# STM32F4xxZ.net
KiCad netlist of a schematic drawn in Altium Designer
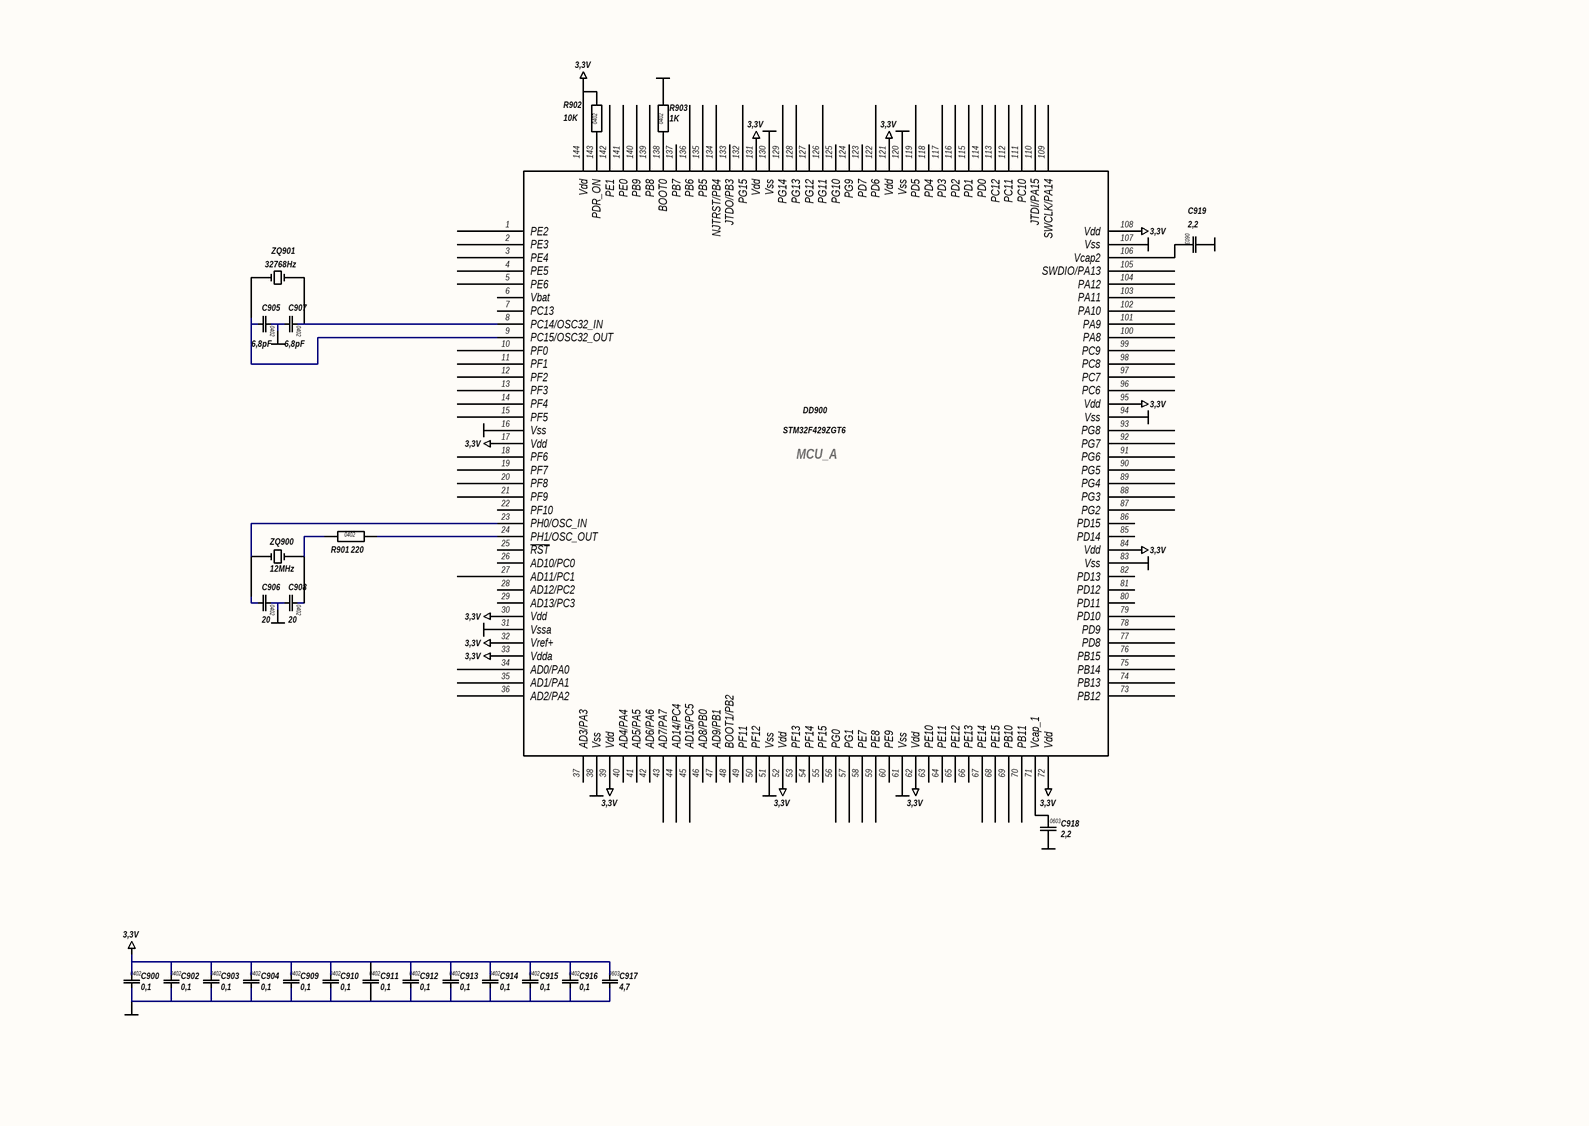
[diagram p0: STM32F4xxZ.SchDoc]

(export (version "E")
  (design (tool "Eeschema 10.0.6"))
  (components
    (comp (ref "C900")
      (value "0,1")
      (footprint "CAP0402")
      (description "Конденсатор чип")
      (libsource (lib "EwgPassive") (part "CAP_0402"))
    )
    (comp (ref "C902")
      (value "0,1")
      (footprint "CAP0402")
      (description "Конденсатор чип")
      (libsource (lib "EwgPassive") (part "CAP_0402"))
    )
    (comp (ref "C903")
      (value "0,1")
      (footprint "CAP0402")
      (description "Конденсатор чип")
      (libsource (lib "EwgPassive") (part "CAP_0402"))
    )
    (comp (ref "C904")
      (value "0,1")
      (footprint "CAP0402")
      (description "Конденсатор чип")
      (libsource (lib "EwgPassive") (part "CAP_0402"))
    )
    (comp (ref "C905")
      (value "6,8pF")
      (footprint "CAP0402")
      (description "Конденсатор чип")
      (libsource (lib "EwgPassive") (part "CAP_0402"))
    )
    (comp (ref "C906")
      (value "20")
      (footprint "CAP0402")
      (description "Конденсатор чип")
      (libsource (lib "EwgPassive") (part "CAP_0402"))
    )
    (comp (ref "C907")
      (value "6,8pF")
      (footprint "CAP0402")
      (description "Конденсатор чип")
      (libsource (lib "EwgPassive") (part "CAP_0402"))
    )
    (comp (ref "C908")
      (value "20")
      (footprint "CAP0402")
      (description "Конденсатор чип")
      (libsource (lib "EwgPassive") (part "CAP_0402"))
    )
    (comp (ref "C909")
      (value "0,1")
      (footprint "CAP0402")
      (description "Конденсатор чип")
      (libsource (lib "EwgPassive") (part "CAP_0402"))
    )
    (comp (ref "C910")
      (value "0,1")
      (footprint "CAP0402")
      (description "Конденсатор чип")
      (libsource (lib "EwgPassive") (part "CAP_0402"))
    )
    (comp (ref "C911")
      (value "0,1")
      (footprint "CAP0402")
      (description "Конденсатор чип")
      (libsource (lib "EwgPassive") (part "CAP_0402"))
    )
    (comp (ref "C912")
      (value "0,1")
      (footprint "CAP0402")
      (description "Конденсатор чип")
      (libsource (lib "EwgPassive") (part "CAP_0402"))
    )
    (comp (ref "C913")
      (value "0,1")
      (footprint "CAP0402")
      (description "Конденсатор чип")
      (libsource (lib "EwgPassive") (part "CAP_0402"))
    )
    (comp (ref "C914")
      (value "0,1")
      (footprint "CAP0402")
      (description "Конденсатор чип")
      (libsource (lib "EwgPassive") (part "CAP_0402"))
    )
    (comp (ref "C915")
      (value "0,1")
      (footprint "CAP0402")
      (description "Конденсатор чип")
      (libsource (lib "EwgPassive") (part "CAP_0402"))
    )
    (comp (ref "C916")
      (value "0,1")
      (footprint "CAP0402")
      (description "Конденсатор чип")
      (libsource (lib "EwgPassive") (part "CAP_0402"))
    )
    (comp (ref "C917")
      (value "4,7")
      (footprint "CAP0603")
      (description "Конденсатор чип")
      (libsource (lib "EwgPassive") (part "CAP_0603"))
    )
    (comp (ref "C918")
      (value "2,2")
      (footprint "CAP0603")
      (description "Конденсатор чип")
      (libsource (lib "EwgPassive") (part "CAP_0603"))
    )
    (comp (ref "C919")
      (value "2,2")
      (footprint "CAP0603")
      (description "Конденсатор чип")
      (libsource (lib "EwgPassive") (part "CAP_0603"))
    )
    (comp (ref "DD900")
      (value "STM32F429ZGT6")
      (footprint "LQFP144")
      (description "Микроконтроллер")
      (libsource (lib "EwgMicrochips") (part "STM32F4xxZ"))
    )
    (comp (ref "R901")
      (value "220")
      (footprint "RES0402")
      (description "Резистор чип")
      (libsource (lib "EwgPassive") (part "RES_0402"))
    )
    (comp (ref "R902")
      (value "10K")
      (footprint "RES0402")
      (description "Резистор чип")
      (libsource (lib "EwgPassive") (part "RES_0402"))
    )
    (comp (ref "R903")
      (value "1K")
      (footprint "RES0402")
      (description "Резистор чип")
      (libsource (lib "") (part "RES_0402_1"))
    )
    (comp (ref "ZQ900")
      (value "12MHz")
      (footprint "KX-7")
      (description "Кварц")
      (libsource (lib "EwgPassive") (part "KX-7"))
    )
    (comp (ref "ZQ901")
      (value "32768Hz")
      (footprint "OSC РК206 AA SMD")
      (description "Кварц")
      (libsource (lib "EwgPassive") (part "OSC РК206 AA 32.768KHZ"))
    )
  )
  (nets
    (net (code "1") (name "3,3V") (class "Default")
      (node (ref "C900") (pin "1") (pintype "passive"))
      (node (ref "C902") (pin "1") (pintype "passive"))
      (node (ref "C903") (pin "1") (pintype "passive"))
      (node (ref "C904") (pin "1") (pintype "passive"))
      (node (ref "C909") (pin "1") (pintype "passive"))
      (node (ref "C910") (pin "1") (pintype "passive"))
      (node (ref "C911") (pin "1") (pintype "passive"))
      (node (ref "C912") (pin "1") (pintype "passive"))
      (node (ref "C913") (pin "1") (pintype "passive"))
      (node (ref "C914") (pin "1") (pintype "passive"))
      (node (ref "C915") (pin "1") (pintype "passive"))
      (node (ref "C916") (pin "1") (pintype "passive"))
      (node (ref "C917") (pin "1") (pintype "passive"))
      (node (ref "DD900") (pin "108") (pinfunction "Vdd_108") (pintype "passive"))
      (node (ref "DD900") (pin "121") (pinfunction "Vdd_121") (pintype "passive"))
      (node (ref "DD900") (pin "131") (pinfunction "Vdd_131") (pintype "passive"))
      (node (ref "DD900") (pin "144") (pinfunction "Vdd_144") (pintype "passive"))
      (node (ref "DD900") (pin "17") (pinfunction "Vdd_17") (pintype "passive"))
      (node (ref "DD900") (pin "30") (pinfunction "Vdd_30") (pintype "passive"))
      (node (ref "DD900") (pin "32") (pinfunction "Vref+_32") (pintype "passive"))
      (node (ref "DD900") (pin "33") (pinfunction "Vdda_33") (pintype "passive"))
      (node (ref "DD900") (pin "39") (pinfunction "Vdd_39") (pintype "passive"))
      (node (ref "DD900") (pin "52") (pinfunction "Vdd_52") (pintype "passive"))
      (node (ref "DD900") (pin "62") (pinfunction "Vdd_62") (pintype "passive"))
      (node (ref "DD900") (pin "72") (pinfunction "Vdd_72") (pintype "passive"))
      (node (ref "DD900") (pin "84") (pinfunction "Vdd_84") (pintype "passive"))
      (node (ref "DD900") (pin "95") (pinfunction "Vdd_95") (pintype "passive"))
      (node (ref "R902") (pin "2") (pintype "passive"))
    )
    (net (code "2") (name "GND") (class "Default")
      (node (ref "C900") (pin "2") (pintype "passive"))
      (node (ref "C902") (pin "2") (pintype "passive"))
      (node (ref "C903") (pin "2") (pintype "passive"))
      (node (ref "C904") (pin "2") (pintype "passive"))
      (node (ref "C905") (pin "1") (pintype "passive"))
      (node (ref "C906") (pin "1") (pintype "passive"))
      (node (ref "C907") (pin "2") (pintype "passive"))
      (node (ref "C908") (pin "2") (pintype "passive"))
      (node (ref "C909") (pin "2") (pintype "passive"))
      (node (ref "C910") (pin "2") (pintype "passive"))
      (node (ref "C911") (pin "2") (pintype "passive"))
      (node (ref "C912") (pin "2") (pintype "passive"))
      (node (ref "C913") (pin "2") (pintype "passive"))
      (node (ref "C914") (pin "2") (pintype "passive"))
      (node (ref "C915") (pin "2") (pintype "passive"))
      (node (ref "C916") (pin "2") (pintype "passive"))
      (node (ref "C917") (pin "2") (pintype "passive"))
      (node (ref "C918") (pin "2") (pintype "passive"))
      (node (ref "C919") (pin "2") (pintype "passive"))
      (node (ref "DD900") (pin "107") (pinfunction "Vss_107") (pintype "passive"))
      (node (ref "DD900") (pin "120") (pinfunction "Vss_120") (pintype "passive"))
      (node (ref "DD900") (pin "130") (pinfunction "Vss_130") (pintype "passive"))
      (node (ref "DD900") (pin "16") (pinfunction "Vss_16") (pintype "passive"))
      (node (ref "DD900") (pin "31") (pinfunction "Vssa_31") (pintype "passive"))
      (node (ref "DD900") (pin "38") (pinfunction "Vss_38") (pintype "passive"))
      (node (ref "DD900") (pin "51") (pinfunction "Vss_51") (pintype "passive"))
      (node (ref "DD900") (pin "61") (pinfunction "Vss_61") (pintype "passive"))
      (node (ref "DD900") (pin "83") (pinfunction "Vss_83") (pintype "passive"))
      (node (ref "DD900") (pin "94") (pinfunction "Vss_94") (pintype "passive"))
      (node (ref "R903") (pin "2") (pintype "passive"))
    )
    (net (code "3") (name "Net-(C908-Pad1)") (class "Default")
      (node (ref "C908") (pin "1") (pintype "passive"))
      (node (ref "R901") (pin "1") (pintype "passive"))
      (node (ref "ZQ900") (pin "1") (pintype "passive"))
    )
    (net (code "4") (name "Net-(DD900-BOOT0)") (class "Default")
      (node (ref "DD900") (pin "138") (pinfunction "BOOT0_138") (pintype "passive"))
      (node (ref "R903") (pin "1") (pintype "passive"))
    )
    (net (code "5") (name "Net-(DD900-PC14{slash}OSC32_IN)") (class "Default")
      (node (ref "C907") (pin "1") (pintype "passive"))
      (node (ref "DD900") (pin "8") (pinfunction "PC14/OSC32_IN_8") (pintype "passive"))
      (node (ref "ZQ901") (pin "1") (pintype "passive"))
    )
    (net (code "6") (name "Net-(DD900-PC15{slash}OSC32_OUT)") (class "Default")
      (node (ref "C905") (pin "2") (pintype "passive"))
      (node (ref "DD900") (pin "9") (pinfunction "PC15/OSC32_OUT_9") (pintype "passive"))
      (node (ref "ZQ901") (pin "2") (pintype "passive"))
    )
    (net (code "7") (name "Net-(DD900-PDR_ON)") (class "Default")
      (node (ref "DD900") (pin "143") (pinfunction "PDR_ON_143") (pintype "passive"))
      (node (ref "R902") (pin "1") (pintype "passive"))
    )
    (net (code "8") (name "Net-(DD900-PH0{slash}OSC_IN)") (class "Default")
      (node (ref "C906") (pin "2") (pintype "passive"))
      (node (ref "DD900") (pin "23") (pinfunction "PH0/OSC_IN_23") (pintype "passive"))
      (node (ref "ZQ900") (pin "3") (pintype "passive"))
    )
    (net (code "9") (name "Net-(DD900-PH1{slash}OSC_OUT)") (class "Default")
      (node (ref "DD900") (pin "24") (pinfunction "PH1/OSC_OUT_24") (pintype "passive"))
      (node (ref "R901") (pin "2") (pintype "passive"))
    )
    (net (code "10") (name "Net-(DD900-Vcap2)") (class "Default")
      (node (ref "C919") (pin "1") (pintype "passive"))
      (node (ref "DD900") (pin "106") (pinfunction "Vcap2_106") (pintype "passive"))
    )
    (net (code "11") (name "Net-(DD900-Vcap_1)") (class "Default")
      (node (ref "C918") (pin "1") (pintype "passive"))
      (node (ref "DD900") (pin "71") (pinfunction "Vcap_1_71") (pintype "passive"))
    )
    (net (code "12") (name "unconnected-(DD900-AD0{slash}PA0-Pad34)") (class "Default")
      (node (ref "DD900") (pin "34") (pinfunction "AD0/PA0_34") (pintype "passive"))
    )
    (net (code "13") (name "unconnected-(DD900-AD1{slash}PA1-Pad35)") (class "Default")
      (node (ref "DD900") (pin "35") (pinfunction "AD1/PA1_35") (pintype "passive"))
    )
    (net (code "14") (name "unconnected-(DD900-AD2{slash}PA2-Pad36)") (class "Default")
      (node (ref "DD900") (pin "36") (pinfunction "AD2/PA2_36") (pintype "passive"))
    )
    (net (code "15") (name "unconnected-(DD900-AD3{slash}PA3-Pad37)") (class "Default")
      (node (ref "DD900") (pin "37") (pinfunction "AD3/PA3_37") (pintype "passive"))
    )
    (net (code "16") (name "unconnected-(DD900-AD4{slash}PA4-Pad40)") (class "Default")
      (node (ref "DD900") (pin "40") (pinfunction "AD4/PA4_40") (pintype "passive"))
    )
    (net (code "17") (name "unconnected-(DD900-AD5{slash}PA5-Pad41)") (class "Default")
      (node (ref "DD900") (pin "41") (pinfunction "AD5/PA5_41") (pintype "passive"))
    )
    (net (code "18") (name "unconnected-(DD900-AD6{slash}PA6-Pad42)") (class "Default")
      (node (ref "DD900") (pin "42") (pinfunction "AD6/PA6_42") (pintype "passive"))
    )
    (net (code "19") (name "unconnected-(DD900-AD7{slash}PA7-Pad43)") (class "Default")
      (node (ref "DD900") (pin "43") (pinfunction "AD7/PA7_43") (pintype "passive"))
    )
    (net (code "20") (name "unconnected-(DD900-AD8{slash}PB0-Pad46)") (class "Default")
      (node (ref "DD900") (pin "46") (pinfunction "AD8/PB0_46") (pintype "passive"))
    )
    (net (code "21") (name "unconnected-(DD900-AD9{slash}PB1-Pad47)") (class "Default")
      (node (ref "DD900") (pin "47") (pinfunction "AD9/PB1_47") (pintype "passive"))
    )
    (net (code "22") (name "unconnected-(DD900-AD10{slash}PC0-Pad26)") (class "Default")
      (node (ref "DD900") (pin "26") (pinfunction "AD10/PC0_26") (pintype "passive"))
    )
    (net (code "23") (name "unconnected-(DD900-AD11{slash}PC1-Pad27)") (class "Default")
      (node (ref "DD900") (pin "27") (pinfunction "AD11/PC1_27") (pintype "passive"))
    )
    (net (code "24") (name "unconnected-(DD900-AD12{slash}PC2-Pad28)") (class "Default")
      (node (ref "DD900") (pin "28") (pinfunction "AD12/PC2_28") (pintype "passive"))
    )
    (net (code "25") (name "unconnected-(DD900-AD13{slash}PC3-Pad29)") (class "Default")
      (node (ref "DD900") (pin "29") (pinfunction "AD13/PC3_29") (pintype "passive"))
    )
    (net (code "26") (name "unconnected-(DD900-AD14{slash}PC4-Pad44)") (class "Default")
      (node (ref "DD900") (pin "44") (pinfunction "AD14/PC4_44") (pintype "passive"))
    )
    (net (code "27") (name "unconnected-(DD900-AD15{slash}PC5-Pad45)") (class "Default")
      (node (ref "DD900") (pin "45") (pinfunction "AD15/PC5_45") (pintype "passive"))
    )
    (net (code "28") (name "unconnected-(DD900-BOOT1{slash}PB2-Pad48)") (class "Default")
      (node (ref "DD900") (pin "48") (pinfunction "BOOT1/PB2_48") (pintype "passive"))
    )
    (net (code "29") (name "unconnected-(DD900-JTDI{slash}PA15-Pad110)") (class "Default")
      (node (ref "DD900") (pin "110") (pinfunction "JTDI/PA15_110") (pintype "passive"))
    )
    (net (code "30") (name "unconnected-(DD900-JTDO{slash}PB3-Pad133)") (class "Default")
      (node (ref "DD900") (pin "133") (pinfunction "JTDO/PB3_133") (pintype "passive"))
    )
    (net (code "31") (name "unconnected-(DD900-NJTRST{slash}PB4-Pad134)") (class "Default")
      (node (ref "DD900") (pin "134") (pinfunction "NJTRST/PB4_134") (pintype "passive"))
    )
    (net (code "32") (name "unconnected-(DD900-PA8-Pad100)") (class "Default")
      (node (ref "DD900") (pin "100") (pinfunction "PA8_100") (pintype "passive"))
    )
    (net (code "33") (name "unconnected-(DD900-PA9-Pad101)") (class "Default")
      (node (ref "DD900") (pin "101") (pinfunction "PA9_101") (pintype "passive"))
    )
    (net (code "34") (name "unconnected-(DD900-PA10-Pad102)") (class "Default")
      (node (ref "DD900") (pin "102") (pinfunction "PA10_102") (pintype "passive"))
    )
    (net (code "35") (name "unconnected-(DD900-PA11-Pad103)") (class "Default")
      (node (ref "DD900") (pin "103") (pinfunction "PA11_103") (pintype "passive"))
    )
    (net (code "36") (name "unconnected-(DD900-PA12-Pad104)") (class "Default")
      (node (ref "DD900") (pin "104") (pinfunction "PA12_104") (pintype "passive"))
    )
    (net (code "37") (name "unconnected-(DD900-PB5-Pad135)") (class "Default")
      (node (ref "DD900") (pin "135") (pinfunction "PB5_135") (pintype "passive"))
    )
    (net (code "38") (name "unconnected-(DD900-PB6-Pad136)") (class "Default")
      (node (ref "DD900") (pin "136") (pinfunction "PB6_136") (pintype "passive"))
    )
    (net (code "39") (name "unconnected-(DD900-PB7-Pad137)") (class "Default")
      (node (ref "DD900") (pin "137") (pinfunction "PB7_137") (pintype "passive"))
    )
    (net (code "40") (name "unconnected-(DD900-PB8-Pad139)") (class "Default")
      (node (ref "DD900") (pin "139") (pinfunction "PB8_139") (pintype "passive"))
    )
    (net (code "41") (name "unconnected-(DD900-PB9-Pad140)") (class "Default")
      (node (ref "DD900") (pin "140") (pinfunction "PB9_140") (pintype "passive"))
    )
    (net (code "42") (name "unconnected-(DD900-PB10-Pad69)") (class "Default")
      (node (ref "DD900") (pin "69") (pinfunction "PB10_69") (pintype "passive"))
    )
    (net (code "43") (name "unconnected-(DD900-PB11-Pad70)") (class "Default")
      (node (ref "DD900") (pin "70") (pinfunction "PB11_70") (pintype "passive"))
    )
    (net (code "44") (name "unconnected-(DD900-PB12-Pad73)") (class "Default")
      (node (ref "DD900") (pin "73") (pinfunction "PB12_73") (pintype "passive"))
    )
    (net (code "45") (name "unconnected-(DD900-PB13-Pad74)") (class "Default")
      (node (ref "DD900") (pin "74") (pinfunction "PB13_74") (pintype "passive"))
    )
    (net (code "46") (name "unconnected-(DD900-PB14-Pad75)") (class "Default")
      (node (ref "DD900") (pin "75") (pinfunction "PB14_75") (pintype "passive"))
    )
    (net (code "47") (name "unconnected-(DD900-PB15-Pad76)") (class "Default")
      (node (ref "DD900") (pin "76") (pinfunction "PB15_76") (pintype "passive"))
    )
    (net (code "48") (name "unconnected-(DD900-PC6-Pad96)") (class "Default")
      (node (ref "DD900") (pin "96") (pinfunction "PC6_96") (pintype "passive"))
    )
    (net (code "49") (name "unconnected-(DD900-PC7-Pad97)") (class "Default")
      (node (ref "DD900") (pin "97") (pinfunction "PC7_97") (pintype "passive"))
    )
    (net (code "50") (name "unconnected-(DD900-PC8-Pad98)") (class "Default")
      (node (ref "DD900") (pin "98") (pinfunction "PC8_98") (pintype "passive"))
    )
    (net (code "51") (name "unconnected-(DD900-PC9-Pad99)") (class "Default")
      (node (ref "DD900") (pin "99") (pinfunction "PC9_99") (pintype "passive"))
    )
    (net (code "52") (name "unconnected-(DD900-PC10-Pad111)") (class "Default")
      (node (ref "DD900") (pin "111") (pinfunction "PC10_111") (pintype "passive"))
    )
    (net (code "53") (name "unconnected-(DD900-PC11-Pad112)") (class "Default")
      (node (ref "DD900") (pin "112") (pinfunction "PC11_112") (pintype "passive"))
    )
    (net (code "54") (name "unconnected-(DD900-PC12-Pad113)") (class "Default")
      (node (ref "DD900") (pin "113") (pinfunction "PC12_113") (pintype "passive"))
    )
    (net (code "55") (name "unconnected-(DD900-PC13-Pad7)") (class "Default")
      (node (ref "DD900") (pin "7") (pinfunction "PC13_7") (pintype "passive"))
    )
    (net (code "56") (name "unconnected-(DD900-PD0-Pad114)") (class "Default")
      (node (ref "DD900") (pin "114") (pinfunction "PD0_114") (pintype "passive"))
    )
    (net (code "57") (name "unconnected-(DD900-PD1-Pad115)") (class "Default")
      (node (ref "DD900") (pin "115") (pinfunction "PD1_115") (pintype "passive"))
    )
    (net (code "58") (name "unconnected-(DD900-PD2-Pad116)") (class "Default")
      (node (ref "DD900") (pin "116") (pinfunction "PD2_116") (pintype "passive"))
    )
    (net (code "59") (name "unconnected-(DD900-PD3-Pad117)") (class "Default")
      (node (ref "DD900") (pin "117") (pinfunction "PD3_117") (pintype "passive"))
    )
    (net (code "60") (name "unconnected-(DD900-PD4-Pad118)") (class "Default")
      (node (ref "DD900") (pin "118") (pinfunction "PD4_118") (pintype "passive"))
    )
    (net (code "61") (name "unconnected-(DD900-PD5-Pad119)") (class "Default")
      (node (ref "DD900") (pin "119") (pinfunction "PD5_119") (pintype "passive"))
    )
    (net (code "62") (name "unconnected-(DD900-PD6-Pad122)") (class "Default")
      (node (ref "DD900") (pin "122") (pinfunction "PD6_122") (pintype "passive"))
    )
    (net (code "63") (name "unconnected-(DD900-PD7-Pad123)") (class "Default")
      (node (ref "DD900") (pin "123") (pinfunction "PD7_123") (pintype "passive"))
    )
    (net (code "64") (name "unconnected-(DD900-PD8-Pad77)") (class "Default")
      (node (ref "DD900") (pin "77") (pinfunction "PD8_77") (pintype "passive"))
    )
    (net (code "65") (name "unconnected-(DD900-PD9-Pad78)") (class "Default")
      (node (ref "DD900") (pin "78") (pinfunction "PD9_78") (pintype "passive"))
    )
    (net (code "66") (name "unconnected-(DD900-PD10-Pad79)") (class "Default")
      (node (ref "DD900") (pin "79") (pinfunction "PD10_79") (pintype "passive"))
    )
    (net (code "67") (name "unconnected-(DD900-PD11-Pad80)") (class "Default")
      (node (ref "DD900") (pin "80") (pinfunction "PD11_80") (pintype "passive"))
    )
    (net (code "68") (name "unconnected-(DD900-PD12-Pad81)") (class "Default")
      (node (ref "DD900") (pin "81") (pinfunction "PD12_81") (pintype "passive"))
    )
    (net (code "69") (name "unconnected-(DD900-PD13-Pad82)") (class "Default")
      (node (ref "DD900") (pin "82") (pinfunction "PD13_82") (pintype "passive"))
    )
    (net (code "70") (name "unconnected-(DD900-PD14-Pad85)") (class "Default")
      (node (ref "DD900") (pin "85") (pinfunction "PD14_85") (pintype "passive"))
    )
    (net (code "71") (name "unconnected-(DD900-PD15-Pad86)") (class "Default")
      (node (ref "DD900") (pin "86") (pinfunction "PD15_86") (pintype "passive"))
    )
    (net (code "72") (name "unconnected-(DD900-PE0-Pad141)") (class "Default")
      (node (ref "DD900") (pin "141") (pinfunction "PE0_141") (pintype "passive"))
    )
    (net (code "73") (name "unconnected-(DD900-PE1-Pad142)") (class "Default")
      (node (ref "DD900") (pin "142") (pinfunction "PE1_142") (pintype "passive"))
    )
    (net (code "74") (name "unconnected-(DD900-PE2-Pad1)") (class "Default")
      (node (ref "DD900") (pin "1") (pinfunction "PE2_1") (pintype "passive"))
    )
    (net (code "75") (name "unconnected-(DD900-PE3-Pad2)") (class "Default")
      (node (ref "DD900") (pin "2") (pinfunction "PE3_2") (pintype "passive"))
    )
    (net (code "76") (name "unconnected-(DD900-PE4-Pad3)") (class "Default")
      (node (ref "DD900") (pin "3") (pinfunction "PE4_3") (pintype "passive"))
    )
    (net (code "77") (name "unconnected-(DD900-PE5-Pad4)") (class "Default")
      (node (ref "DD900") (pin "4") (pinfunction "PE5_4") (pintype "passive"))
    )
    (net (code "78") (name "unconnected-(DD900-PE6-Pad5)") (class "Default")
      (node (ref "DD900") (pin "5") (pinfunction "PE6_5") (pintype "passive"))
    )
    (net (code "79") (name "unconnected-(DD900-PE7-Pad58)") (class "Default")
      (node (ref "DD900") (pin "58") (pinfunction "PE7_58") (pintype "passive"))
    )
    (net (code "80") (name "unconnected-(DD900-PE8-Pad59)") (class "Default")
      (node (ref "DD900") (pin "59") (pinfunction "PE8_59") (pintype "passive"))
    )
    (net (code "81") (name "unconnected-(DD900-PE9-Pad60)") (class "Default")
      (node (ref "DD900") (pin "60") (pinfunction "PE9_60") (pintype "passive"))
    )
    (net (code "82") (name "unconnected-(DD900-PE10-Pad63)") (class "Default")
      (node (ref "DD900") (pin "63") (pinfunction "PE10_63") (pintype "passive"))
    )
    (net (code "83") (name "unconnected-(DD900-PE11-Pad64)") (class "Default")
      (node (ref "DD900") (pin "64") (pinfunction "PE11_64") (pintype "passive"))
    )
    (net (code "84") (name "unconnected-(DD900-PE12-Pad65)") (class "Default")
      (node (ref "DD900") (pin "65") (pinfunction "PE12_65") (pintype "passive"))
    )
    (net (code "85") (name "unconnected-(DD900-PE13-Pad66)") (class "Default")
      (node (ref "DD900") (pin "66") (pinfunction "PE13_66") (pintype "passive"))
    )
    (net (code "86") (name "unconnected-(DD900-PE14-Pad67)") (class "Default")
      (node (ref "DD900") (pin "67") (pinfunction "PE14_67") (pintype "passive"))
    )
    (net (code "87") (name "unconnected-(DD900-PE15-Pad68)") (class "Default")
      (node (ref "DD900") (pin "68") (pinfunction "PE15_68") (pintype "passive"))
    )
    (net (code "88") (name "unconnected-(DD900-PF0-Pad10)") (class "Default")
      (node (ref "DD900") (pin "10") (pinfunction "PF0_10") (pintype "passive"))
    )
    (net (code "89") (name "unconnected-(DD900-PF1-Pad11)") (class "Default")
      (node (ref "DD900") (pin "11") (pinfunction "PF1_11") (pintype "passive"))
    )
    (net (code "90") (name "unconnected-(DD900-PF2-Pad12)") (class "Default")
      (node (ref "DD900") (pin "12") (pinfunction "PF2_12") (pintype "passive"))
    )
    (net (code "91") (name "unconnected-(DD900-PF3-Pad13)") (class "Default")
      (node (ref "DD900") (pin "13") (pinfunction "PF3_13") (pintype "passive"))
    )
    (net (code "92") (name "unconnected-(DD900-PF4-Pad14)") (class "Default")
      (node (ref "DD900") (pin "14") (pinfunction "PF4_14") (pintype "passive"))
    )
    (net (code "93") (name "unconnected-(DD900-PF5-Pad15)") (class "Default")
      (node (ref "DD900") (pin "15") (pinfunction "PF5_15") (pintype "passive"))
    )
    (net (code "94") (name "unconnected-(DD900-PF6-Pad18)") (class "Default")
      (node (ref "DD900") (pin "18") (pinfunction "PF6_18") (pintype "passive"))
    )
    (net (code "95") (name "unconnected-(DD900-PF7-Pad19)") (class "Default")
      (node (ref "DD900") (pin "19") (pinfunction "PF7_19") (pintype "passive"))
    )
    (net (code "96") (name "unconnected-(DD900-PF8-Pad20)") (class "Default")
      (node (ref "DD900") (pin "20") (pinfunction "PF8_20") (pintype "passive"))
    )
    (net (code "97") (name "unconnected-(DD900-PF9-Pad21)") (class "Default")
      (node (ref "DD900") (pin "21") (pinfunction "PF9_21") (pintype "passive"))
    )
    (net (code "98") (name "unconnected-(DD900-PF10-Pad22)") (class "Default")
      (node (ref "DD900") (pin "22") (pinfunction "PF10_22") (pintype "passive"))
    )
    (net (code "99") (name "unconnected-(DD900-PF11-Pad49)") (class "Default")
      (node (ref "DD900") (pin "49") (pinfunction "PF11_49") (pintype "passive"))
    )
    (net (code "100") (name "unconnected-(DD900-PF12-Pad50)") (class "Default")
      (node (ref "DD900") (pin "50") (pinfunction "PF12_50") (pintype "passive"))
    )
    (net (code "101") (name "unconnected-(DD900-PF13-Pad53)") (class "Default")
      (node (ref "DD900") (pin "53") (pinfunction "PF13_53") (pintype "passive"))
    )
    (net (code "102") (name "unconnected-(DD900-PF14-Pad54)") (class "Default")
      (node (ref "DD900") (pin "54") (pinfunction "PF14_54") (pintype "passive"))
    )
    (net (code "103") (name "unconnected-(DD900-PF15-Pad55)") (class "Default")
      (node (ref "DD900") (pin "55") (pinfunction "PF15_55") (pintype "passive"))
    )
    (net (code "104") (name "unconnected-(DD900-PG0-Pad56)") (class "Default")
      (node (ref "DD900") (pin "56") (pinfunction "PG0_56") (pintype "passive"))
    )
    (net (code "105") (name "unconnected-(DD900-PG1-Pad57)") (class "Default")
      (node (ref "DD900") (pin "57") (pinfunction "PG1_57") (pintype "passive"))
    )
    (net (code "106") (name "unconnected-(DD900-PG2-Pad87)") (class "Default")
      (node (ref "DD900") (pin "87") (pinfunction "PG2_87") (pintype "passive"))
    )
    (net (code "107") (name "unconnected-(DD900-PG3-Pad88)") (class "Default")
      (node (ref "DD900") (pin "88") (pinfunction "PG3_88") (pintype "passive"))
    )
    (net (code "108") (name "unconnected-(DD900-PG4-Pad89)") (class "Default")
      (node (ref "DD900") (pin "89") (pinfunction "PG4_89") (pintype "passive"))
    )
    (net (code "109") (name "unconnected-(DD900-PG5-Pad90)") (class "Default")
      (node (ref "DD900") (pin "90") (pinfunction "PG5_90") (pintype "passive"))
    )
    (net (code "110") (name "unconnected-(DD900-PG6-Pad91)") (class "Default")
      (node (ref "DD900") (pin "91") (pinfunction "PG6_91") (pintype "passive"))
    )
    (net (code "111") (name "unconnected-(DD900-PG7-Pad92)") (class "Default")
      (node (ref "DD900") (pin "92") (pinfunction "PG7_92") (pintype "passive"))
    )
    (net (code "112") (name "unconnected-(DD900-PG8-Pad93)") (class "Default")
      (node (ref "DD900") (pin "93") (pinfunction "PG8_93") (pintype "passive"))
    )
    (net (code "113") (name "unconnected-(DD900-PG9-Pad124)") (class "Default")
      (node (ref "DD900") (pin "124") (pinfunction "PG9_124") (pintype "passive"))
    )
    (net (code "114") (name "unconnected-(DD900-PG10-Pad125)") (class "Default")
      (node (ref "DD900") (pin "125") (pinfunction "PG10_125") (pintype "passive"))
    )
    (net (code "115") (name "unconnected-(DD900-PG11-Pad126)") (class "Default")
      (node (ref "DD900") (pin "126") (pinfunction "PG11_126") (pintype "passive"))
    )
    (net (code "116") (name "unconnected-(DD900-PG12-Pad127)") (class "Default")
      (node (ref "DD900") (pin "127") (pinfunction "PG12_127") (pintype "passive"))
    )
    (net (code "117") (name "unconnected-(DD900-PG13-Pad128)") (class "Default")
      (node (ref "DD900") (pin "128") (pinfunction "PG13_128") (pintype "passive"))
    )
    (net (code "118") (name "unconnected-(DD900-PG14-Pad129)") (class "Default")
      (node (ref "DD900") (pin "129") (pinfunction "PG14_129") (pintype "passive"))
    )
    (net (code "119") (name "unconnected-(DD900-PG15-Pad132)") (class "Default")
      (node (ref "DD900") (pin "132") (pinfunction "PG15_132") (pintype "passive"))
    )
    (net (code "120") (name "unconnected-(DD900-SWCLK{slash}PA14-Pad109)") (class "Default")
      (node (ref "DD900") (pin "109") (pinfunction "SWCLK/PA14_109") (pintype "passive"))
    )
    (net (code "121") (name "unconnected-(DD900-SWDIO{slash}PA13-Pad105)") (class "Default")
      (node (ref "DD900") (pin "105") (pinfunction "SWDIO/PA13_105") (pintype "passive"))
    )
    (net (code "122") (name "unconnected-(DD900-Vbat-Pad6)") (class "Default")
      (node (ref "DD900") (pin "6") (pinfunction "Vbat_6") (pintype "passive"))
    )
    (net (code "123") (name "unconnected-(DD900-~{RST}-Pad25)") (class "Default")
      (node (ref "DD900") (pin "25") (pinfunction "~{RST}_25") (pintype "passive"))
    )
    (net (code "124") (name "unconnected-(ZQ900-Pad2)") (class "Default")
      (node (ref "ZQ900") (pin "2") (pintype "passive"))
    )
    (net (code "125") (name "unconnected-(ZQ900-Pad4)") (class "Default")
      (node (ref "ZQ900") (pin "4") (pintype "passive"))
    )
  )
)
